# esp32_c3_demo.net
KiCad netlist of a schematic drawn in Altium Designer
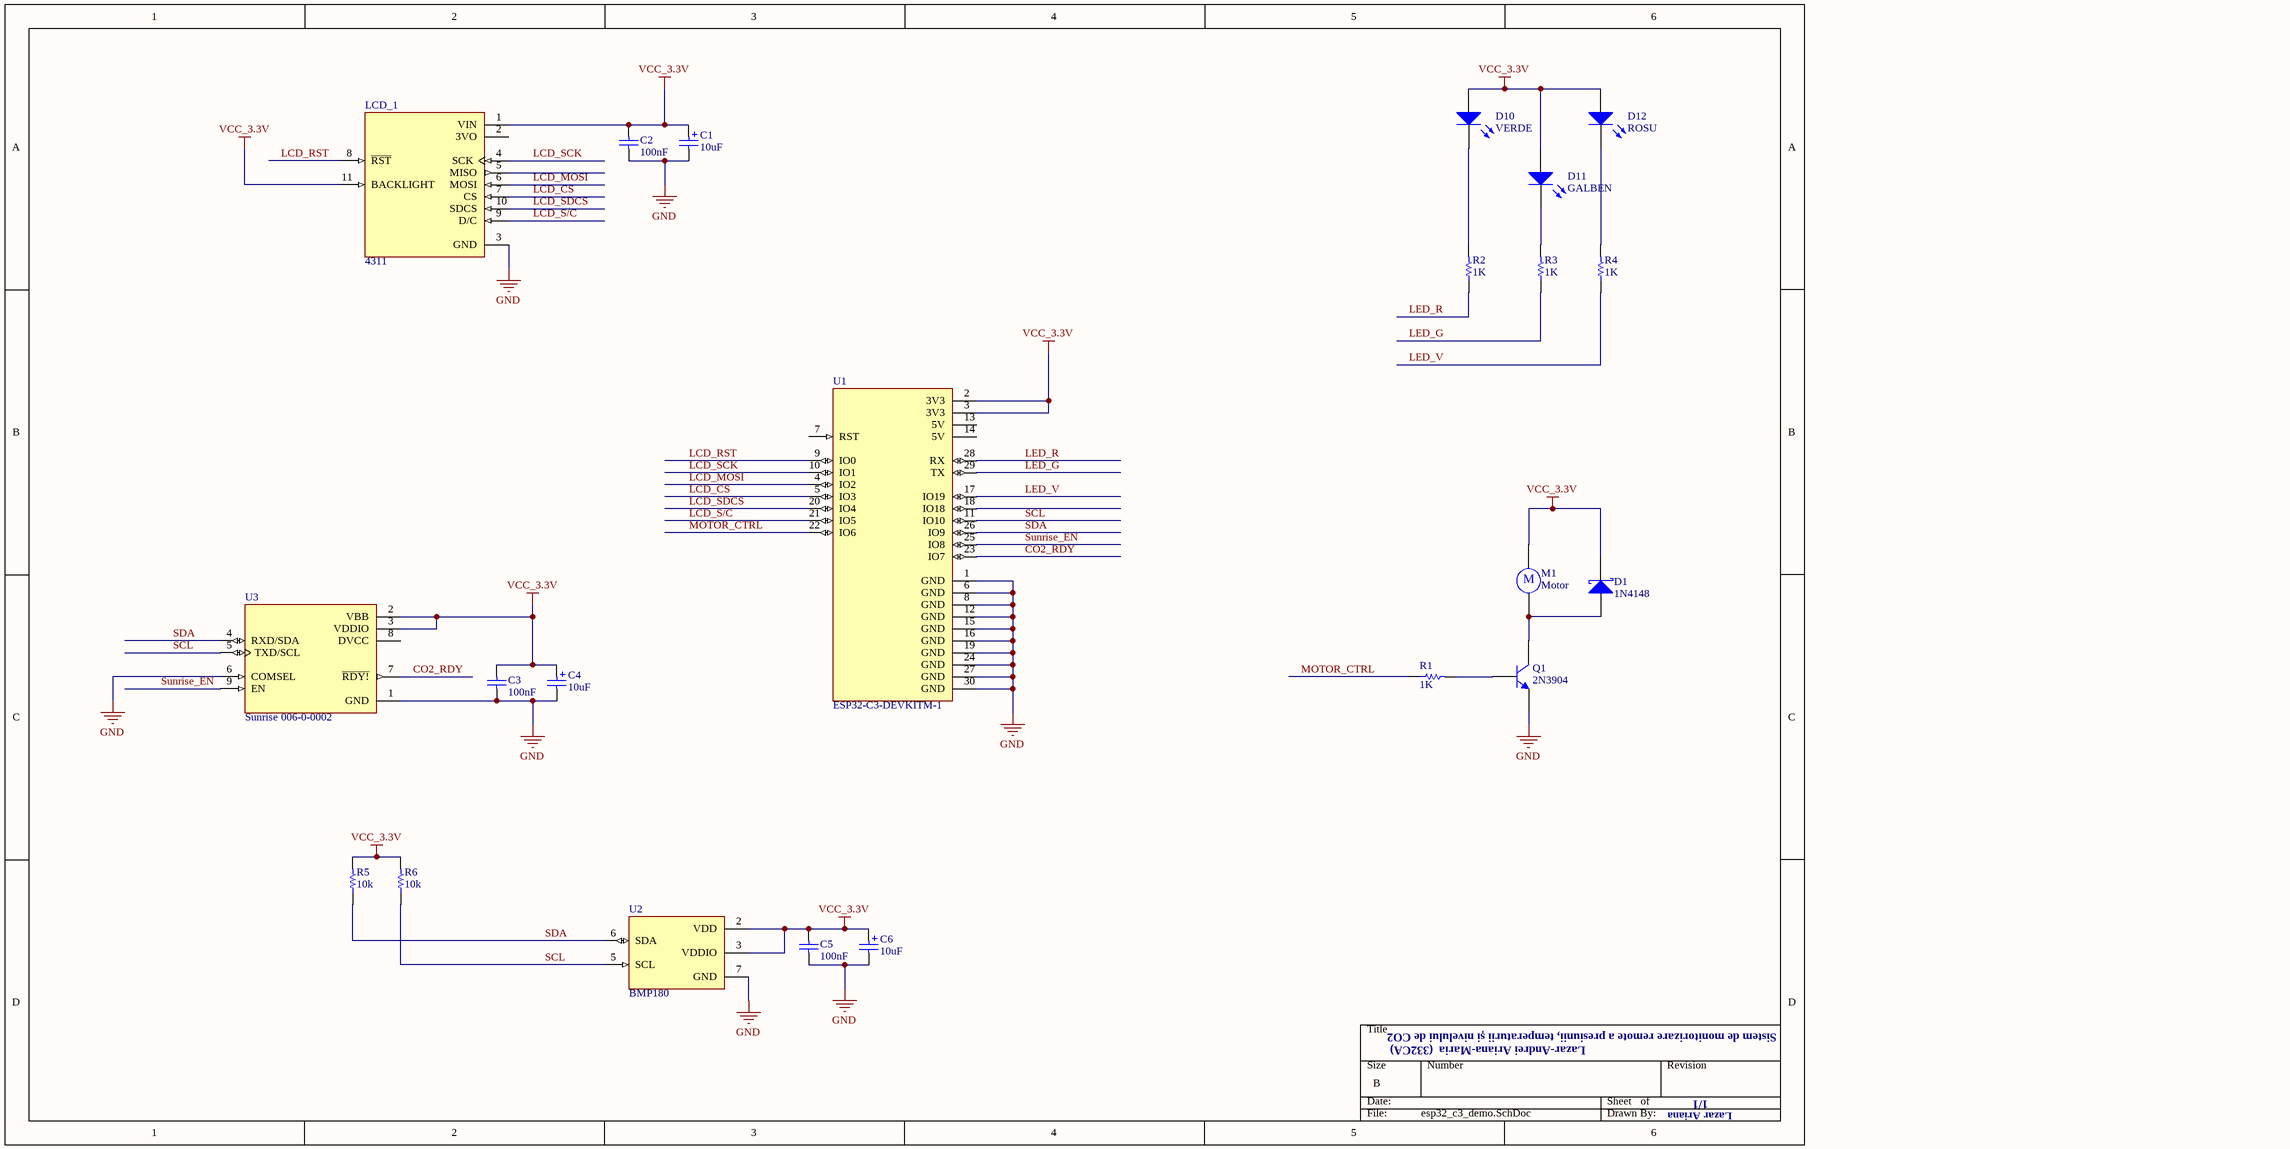
[diagram p0: esp32_c3_demo.SchDoc]

(export (version "E")
  (design (tool "Eeschema 10.0.6"))
  (components
    (comp (ref "C1")
      (value "10uF")
      (footprint "POLAR0.8")
      (description "Polarized Capacitor (Axial)")
      (fields (field (name "Comment") "Cap Pol2") (field (name "PUBLISHER") "Altium Limited"))
      (libsource (lib "Miscellaneous Devices") (part "Cap Pol2"))
    )
    (comp (ref "C2")
      (value "100nF")
      (footprint "RAD-0.3")
      (description "Capacitor")
      (fields (field (name "Comment") "Cap") (field (name "PUBLISHER") "Altium Limited"))
      (libsource (lib "Miscellaneous Devices") (part "Cap"))
    )
    (comp (ref "C3")
      (value "100nF")
      (footprint "RAD-0.3")
      (description "Capacitor")
      (fields (field (name "Comment") "Cap") (field (name "PUBLISHER") "Altium Limited"))
      (libsource (lib "Miscellaneous Devices") (part "Cap"))
    )
    (comp (ref "C4")
      (value "10uF")
      (footprint "POLAR0.8")
      (description "Polarized Capacitor (Axial)")
      (fields (field (name "Comment") "Cap Pol2") (field (name "PUBLISHER") "Altium Limited"))
      (libsource (lib "Miscellaneous Devices") (part "Cap Pol2"))
    )
    (comp (ref "C5")
      (value "100nF")
      (footprint "RAD-0.3")
      (description "Capacitor")
      (fields (field (name "Comment") "Cap") (field (name "PUBLISHER") "Altium Limited"))
      (libsource (lib "Miscellaneous Devices") (part "Cap"))
    )
    (comp (ref "C6")
      (value "10uF")
      (footprint "POLAR0.8")
      (description "Polarized Capacitor (Axial)")
      (fields (field (name "Comment") "Cap Pol2") (field (name "PUBLISHER") "Altium Limited"))
      (libsource (lib "Miscellaneous Devices") (part "Cap Pol2"))
    )
    (comp (ref "D1")
      (value "1N4148")
      (footprint "SMB")
      (description "Schottky Diode")
      (fields (field (name "PUBLISHER") "Altium Limited"))
      (libsource (lib "Miscellaneous Devices") (part "D Schottky"))
    )
    (comp (ref "D10")
      (value "VERDE")
      (footprint "LED-0")
      (description "Typical INFRARED GaAs LED")
      (fields (field (name "PUBLISHER") "Altium Limited"))
      (libsource (lib "Miscellaneous Devices") (part "LED0"))
    )
    (comp (ref "D11")
      (value "GALBEN")
      (footprint "LED-0")
      (description "Typical INFRARED GaAs LED")
      (fields (field (name "PUBLISHER") "Altium Limited"))
      (libsource (lib "Miscellaneous Devices") (part "LED0"))
    )
    (comp (ref "D12")
      (value "ROSU")
      (footprint "LED-0")
      (description "Typical INFRARED GaAs LED")
      (fields (field (name "PUBLISHER") "Altium Limited"))
      (libsource (lib "Miscellaneous Devices") (part "LED0"))
    )
    (comp (ref "LCD_1")
      (value "4311")
      (footprint "MODULE_4311")
      (fields (field (name "MF") "Adafruit Industries LLC"))
      (libsource (lib "4311") (part "4311"))
    )
    (comp (ref "M1")
      (value "Motor")
      (footprint "RB5-10.5")
      (description "Motor, General Kind")
      (fields (field (name "PUBLISHER") "Altium Limited"))
      (libsource (lib "Miscellaneous Devices") (part "Motor"))
    )
    (comp (ref "Q1")
      (value "2N3904")
      (footprint "TO-92A")
      (description "NPN General Purpose Amplifier")
      (fields (field (name "PUBLISHER") "Altium Limited"))
      (libsource (lib "Miscellaneous Devices") (part "2N3904"))
    )
    (comp (ref "R1")
      (value "1K")
      (footprint "AXIAL-0.3")
      (description "Resistor")
      (fields (field (name "Comment") "Res1") (field (name "PUBLISHER") "Altium Limited"))
      (libsource (lib "Miscellaneous Devices") (part "Res1"))
    )
    (comp (ref "R2")
      (value "1K")
      (footprint "AXIAL-0.3")
      (description "Resistor")
      (fields (field (name "Comment") "Res1") (field (name "PUBLISHER") "Altium Limited"))
      (libsource (lib "Miscellaneous Devices") (part "Res1"))
    )
    (comp (ref "R3")
      (value "1K")
      (footprint "AXIAL-0.3")
      (description "Resistor")
      (fields (field (name "Comment") "Res1") (field (name "PUBLISHER") "Altium Limited"))
      (libsource (lib "Miscellaneous Devices") (part "Res1"))
    )
    (comp (ref "R4")
      (value "1K")
      (footprint "AXIAL-0.3")
      (description "Resistor")
      (fields (field (name "Comment") "Res1") (field (name "PUBLISHER") "Altium Limited"))
      (libsource (lib "Miscellaneous Devices") (part "Res1"))
    )
    (comp (ref "R5")
      (value "10k")
      (footprint "AXIAL-0.3")
      (description "Resistor")
      (fields (field (name "Comment") "Res1") (field (name "PUBLISHER") "Altium Limited"))
      (libsource (lib "Miscellaneous Devices") (part "Res1"))
    )
    (comp (ref "R6")
      (value "10k")
      (footprint "AXIAL-0.3")
      (description "Resistor")
      (fields (field (name "Comment") "Res1") (field (name "PUBLISHER") "Altium Limited"))
      (libsource (lib "Miscellaneous Devices") (part "Res1"))
    )
    (comp (ref "U1")
      (value "ESP32-C3-DEVKITM-1")
      (footprint "XCVR_ESP32-C3-DEVKITM-1")
      (fields (field (name "MF") "Espressif Systems"))
      (libsource (lib "ESP32-C3-DEVKITM-1") (part "ESP32-C3-DEVKITM-1"))
    )
    (comp (ref "U2")
      (value "BMP180")
      (footprint "BMP180")
      (description "Pressure Sensor 4.35PSI ~ 15.95PSI (30kPa ~ 110kPa) Absolute - 16 ~ 19 b 7-VLGA")
      (fields (field (name "MF") "Bosch"))
      (libsource (lib "BMP180") (part "BMP180"))
    )
    (comp (ref "U3")
      (value "Sunrise 006-0-0002")
      (footprint "XDCR_006-0-0002")
      (description "Carbon Dioxide (CO2) Sensor")
      (fields (field (name "MF") "Senseair North America Inc.") (field (name "MP") "006-0-0002"))
      (libsource (lib "006-0-0002") (part "006-0-0002"))
    )
  )
  (nets
    (net (code "1") (name "/CO2_RDY") (class "Default")
      (node (ref "U1") (pin "23") (pinfunction "IO7_23") (pintype "bidirectional"))
      (node (ref "U3") (pin "7") (pinfunction "~{RDY!}_7") (pintype "output"))
    )
    (net (code "2") (name "/LCD_CS") (class "Default")
      (node (ref "LCD_1") (pin "7") (pinfunction "CS_7") (pintype "input"))
      (node (ref "U1") (pin "5") (pinfunction "IO3_5") (pintype "bidirectional"))
    )
    (net (code "3") (name "/LCD_MOSI") (class "Default")
      (node (ref "LCD_1") (pin "6") (pinfunction "MOSI_6") (pintype "input"))
      (node (ref "U1") (pin "4") (pinfunction "IO2_4") (pintype "bidirectional"))
    )
    (net (code "4") (name "/LCD_RST") (class "Default")
      (node (ref "LCD_1") (pin "8") (pinfunction "~{RST}_8") (pintype "input"))
      (node (ref "U1") (pin "9") (pinfunction "IO0_9") (pintype "bidirectional"))
    )
    (net (code "5") (name "/LCD_SCK") (class "Default")
      (node (ref "LCD_1") (pin "4") (pinfunction "SCK_4") (pintype "input"))
      (node (ref "U1") (pin "10") (pinfunction "IO1_10") (pintype "bidirectional"))
    )
    (net (code "6") (name "/LCD_SDCS") (class "Default")
      (node (ref "LCD_1") (pin "10") (pinfunction "SDCS_10") (pintype "input"))
      (node (ref "U1") (pin "20") (pinfunction "IO4_20") (pintype "bidirectional"))
    )
    (net (code "7") (name "/LCD_S{slash}C") (class "Default")
      (node (ref "LCD_1") (pin "9") (pinfunction "D/C_9") (pintype "input"))
      (node (ref "U1") (pin "21") (pinfunction "IO5_21") (pintype "bidirectional"))
    )
    (net (code "8") (name "/LED_G") (class "Default")
      (node (ref "R3") (pin "1") (pinfunction "1_1") (pintype "passive"))
      (node (ref "U1") (pin "29") (pinfunction "TX_29") (pintype "bidirectional"))
    )
    (net (code "9") (name "/LED_R") (class "Default")
      (node (ref "R2") (pin "1") (pinfunction "1_1") (pintype "passive"))
      (node (ref "U1") (pin "28") (pinfunction "RX_28") (pintype "bidirectional"))
    )
    (net (code "10") (name "/LED_V") (class "Default")
      (node (ref "R4") (pin "1") (pinfunction "1_1") (pintype "passive"))
      (node (ref "U1") (pin "17") (pinfunction "IO19_17") (pintype "bidirectional"))
    )
    (net (code "11") (name "/MOTOR_CTRL") (class "Default")
      (node (ref "R1") (pin "1") (pinfunction "1_1") (pintype "passive"))
      (node (ref "U1") (pin "22") (pinfunction "IO6_22") (pintype "bidirectional"))
    )
    (net (code "12") (name "/SCL") (class "Default")
      (node (ref "R6") (pin "1") (pinfunction "1_1") (pintype "passive"))
      (node (ref "U1") (pin "11") (pinfunction "IO10_11") (pintype "bidirectional"))
      (node (ref "U2") (pin "5") (pinfunction "SCL_5") (pintype "input"))
      (node (ref "U3") (pin "5") (pinfunction "TXD/SCL_5") (pintype "bidirectional"))
    )
    (net (code "13") (name "/SDA") (class "Default")
      (node (ref "R5") (pin "1") (pinfunction "1_1") (pintype "passive"))
      (node (ref "U1") (pin "26") (pinfunction "IO9_26") (pintype "bidirectional"))
      (node (ref "U2") (pin "6") (pinfunction "SDA_6") (pintype "bidirectional"))
      (node (ref "U3") (pin "4") (pinfunction "RXD/SDA_4") (pintype "bidirectional"))
    )
    (net (code "14") (name "/Sunrise_EN") (class "Default")
      (node (ref "U1") (pin "25") (pinfunction "IO8_25") (pintype "bidirectional"))
      (node (ref "U3") (pin "9") (pinfunction "EN_9") (pintype "input"))
    )
    (net (code "15") (name "GND") (class "Default")
      (node (ref "C1") (pin "2") (pinfunction "2_2") (pintype "passive"))
      (node (ref "C2") (pin "1") (pinfunction "1_1") (pintype "passive"))
      (node (ref "C3") (pin "1") (pinfunction "1_1") (pintype "passive"))
      (node (ref "C4") (pin "2") (pinfunction "2_2") (pintype "passive"))
      (node (ref "C5") (pin "1") (pinfunction "1_1") (pintype "passive"))
      (node (ref "C6") (pin "2") (pinfunction "2_2") (pintype "passive"))
      (node (ref "LCD_1") (pin "3") (pinfunction "GND_3") (pintype "power_in"))
      (node (ref "Q1") (pin "1") (pinfunction "E_1") (pintype "passive"))
      (node (ref "U1") (pin "1") (pinfunction "GND_1") (pintype "power_in"))
      (node (ref "U1") (pin "12") (pinfunction "GND_12") (pintype "power_in"))
      (node (ref "U1") (pin "15") (pinfunction "GND_15") (pintype "power_in"))
      (node (ref "U1") (pin "16") (pinfunction "GND_16") (pintype "power_in"))
      (node (ref "U1") (pin "19") (pinfunction "GND_19") (pintype "power_in"))
      (node (ref "U1") (pin "24") (pinfunction "GND_24") (pintype "power_in"))
      (node (ref "U1") (pin "27") (pinfunction "GND_27") (pintype "power_in"))
      (node (ref "U1") (pin "30") (pinfunction "GND_30") (pintype "power_in"))
      (node (ref "U1") (pin "6") (pinfunction "GND_6") (pintype "power_in"))
      (node (ref "U1") (pin "8") (pinfunction "GND_8") (pintype "power_in"))
      (node (ref "U2") (pin "7") (pinfunction "GND_7") (pintype "power_in"))
      (node (ref "U3") (pin "1") (pinfunction "GND_1") (pintype "power_in"))
      (node (ref "U3") (pin "6") (pinfunction "COMSEL_6") (pintype "input"))
    )
    (net (code "16") (name "Net-(D1-A)") (class "Default")
      (node (ref "D1") (pin "1") (pinfunction "A_1") (pintype "passive"))
      (node (ref "M1") (pin "2") (pinfunction "2_2") (pintype "passive"))
      (node (ref "Q1") (pin "3") (pinfunction "C_3") (pintype "passive"))
    )
    (net (code "17") (name "Net-(D10-K)") (class "Default")
      (node (ref "D10") (pin "2") (pinfunction "K_2") (pintype "passive"))
      (node (ref "R2") (pin "2") (pinfunction "2_2") (pintype "passive"))
    )
    (net (code "18") (name "Net-(D11-K)") (class "Default")
      (node (ref "D11") (pin "2") (pinfunction "K_2") (pintype "passive"))
      (node (ref "R3") (pin "2") (pinfunction "2_2") (pintype "passive"))
    )
    (net (code "19") (name "Net-(D12-K)") (class "Default")
      (node (ref "D12") (pin "2") (pinfunction "K_2") (pintype "passive"))
      (node (ref "R4") (pin "2") (pinfunction "2_2") (pintype "passive"))
    )
    (net (code "20") (name "Net-(Q1-B)") (class "Default")
      (node (ref "Q1") (pin "2") (pinfunction "B_2") (pintype "passive"))
      (node (ref "R1") (pin "2") (pinfunction "2_2") (pintype "passive"))
    )
    (net (code "21") (name "VCC_3.3V") (class "Default")
      (node (ref "C1") (pin "1") (pinfunction "1_1") (pintype "passive"))
      (node (ref "C2") (pin "2") (pinfunction "2_2") (pintype "passive"))
      (node (ref "C3") (pin "2") (pinfunction "2_2") (pintype "passive"))
      (node (ref "C4") (pin "1") (pinfunction "1_1") (pintype "passive"))
      (node (ref "C5") (pin "2") (pinfunction "2_2") (pintype "passive"))
      (node (ref "C6") (pin "1") (pinfunction "1_1") (pintype "passive"))
      (node (ref "D1") (pin "2") (pinfunction "K_2") (pintype "passive"))
      (node (ref "D10") (pin "1") (pinfunction "A_1") (pintype "passive"))
      (node (ref "D11") (pin "1") (pinfunction "A_1") (pintype "passive"))
      (node (ref "D12") (pin "1") (pinfunction "A_1") (pintype "passive"))
      (node (ref "LCD_1") (pin "1") (pinfunction "VIN_1") (pintype "power_in"))
      (node (ref "LCD_1") (pin "11") (pinfunction "BACKLIGHT_11") (pintype "input"))
      (node (ref "M1") (pin "1") (pinfunction "1_1") (pintype "passive"))
      (node (ref "R5") (pin "2") (pinfunction "2_2") (pintype "passive"))
      (node (ref "R6") (pin "2") (pinfunction "2_2") (pintype "passive"))
      (node (ref "U1") (pin "2") (pinfunction "3V3_2") (pintype "power_in"))
      (node (ref "U1") (pin "3") (pinfunction "3V3_3") (pintype "power_in"))
      (node (ref "U2") (pin "2") (pinfunction "VDD_2") (pintype "power_in"))
      (node (ref "U2") (pin "3") (pinfunction "VDDIO_3") (pintype "power_in"))
      (node (ref "U3") (pin "2") (pinfunction "VBB_2") (pintype "power_in"))
      (node (ref "U3") (pin "3") (pinfunction "VDDIO_3") (pintype "power_in"))
    )
    (net (code "22") (name "unconnected-(LCD_1-3VO-Pad2)") (class "Default")
      (node (ref "LCD_1") (pin "2") (pinfunction "3VO_2") (pintype "power_in"))
    )
    (net (code "23") (name "unconnected-(LCD_1-MISO-Pad5)") (class "Default")
      (node (ref "LCD_1") (pin "5") (pinfunction "MISO_5") (pintype "output"))
    )
    (net (code "24") (name "unconnected-(U1-5V-Pad13)") (class "Default")
      (node (ref "U1") (pin "13") (pinfunction "5V_13") (pintype "power_in"))
    )
    (net (code "25") (name "unconnected-(U1-5V-Pad14)") (class "Default")
      (node (ref "U1") (pin "14") (pinfunction "5V_14") (pintype "power_in"))
    )
    (net (code "26") (name "unconnected-(U1-IO18-Pad18)") (class "Default")
      (node (ref "U1") (pin "18") (pinfunction "IO18_18") (pintype "bidirectional"))
    )
    (net (code "27") (name "unconnected-(U1-RST-Pad7)") (class "Default")
      (node (ref "U1") (pin "7") (pinfunction "RST_7") (pintype "input"))
    )
    (net (code "28") (name "unconnected-(U3-DVCC-Pad8)") (class "Default")
      (node (ref "U3") (pin "8") (pinfunction "DVCC_8") (pintype "power_in"))
    )
  )
)
